# 08-DIPSwitches_I2C.net
KiCad netlist of a schematic drawn in Altium Designer
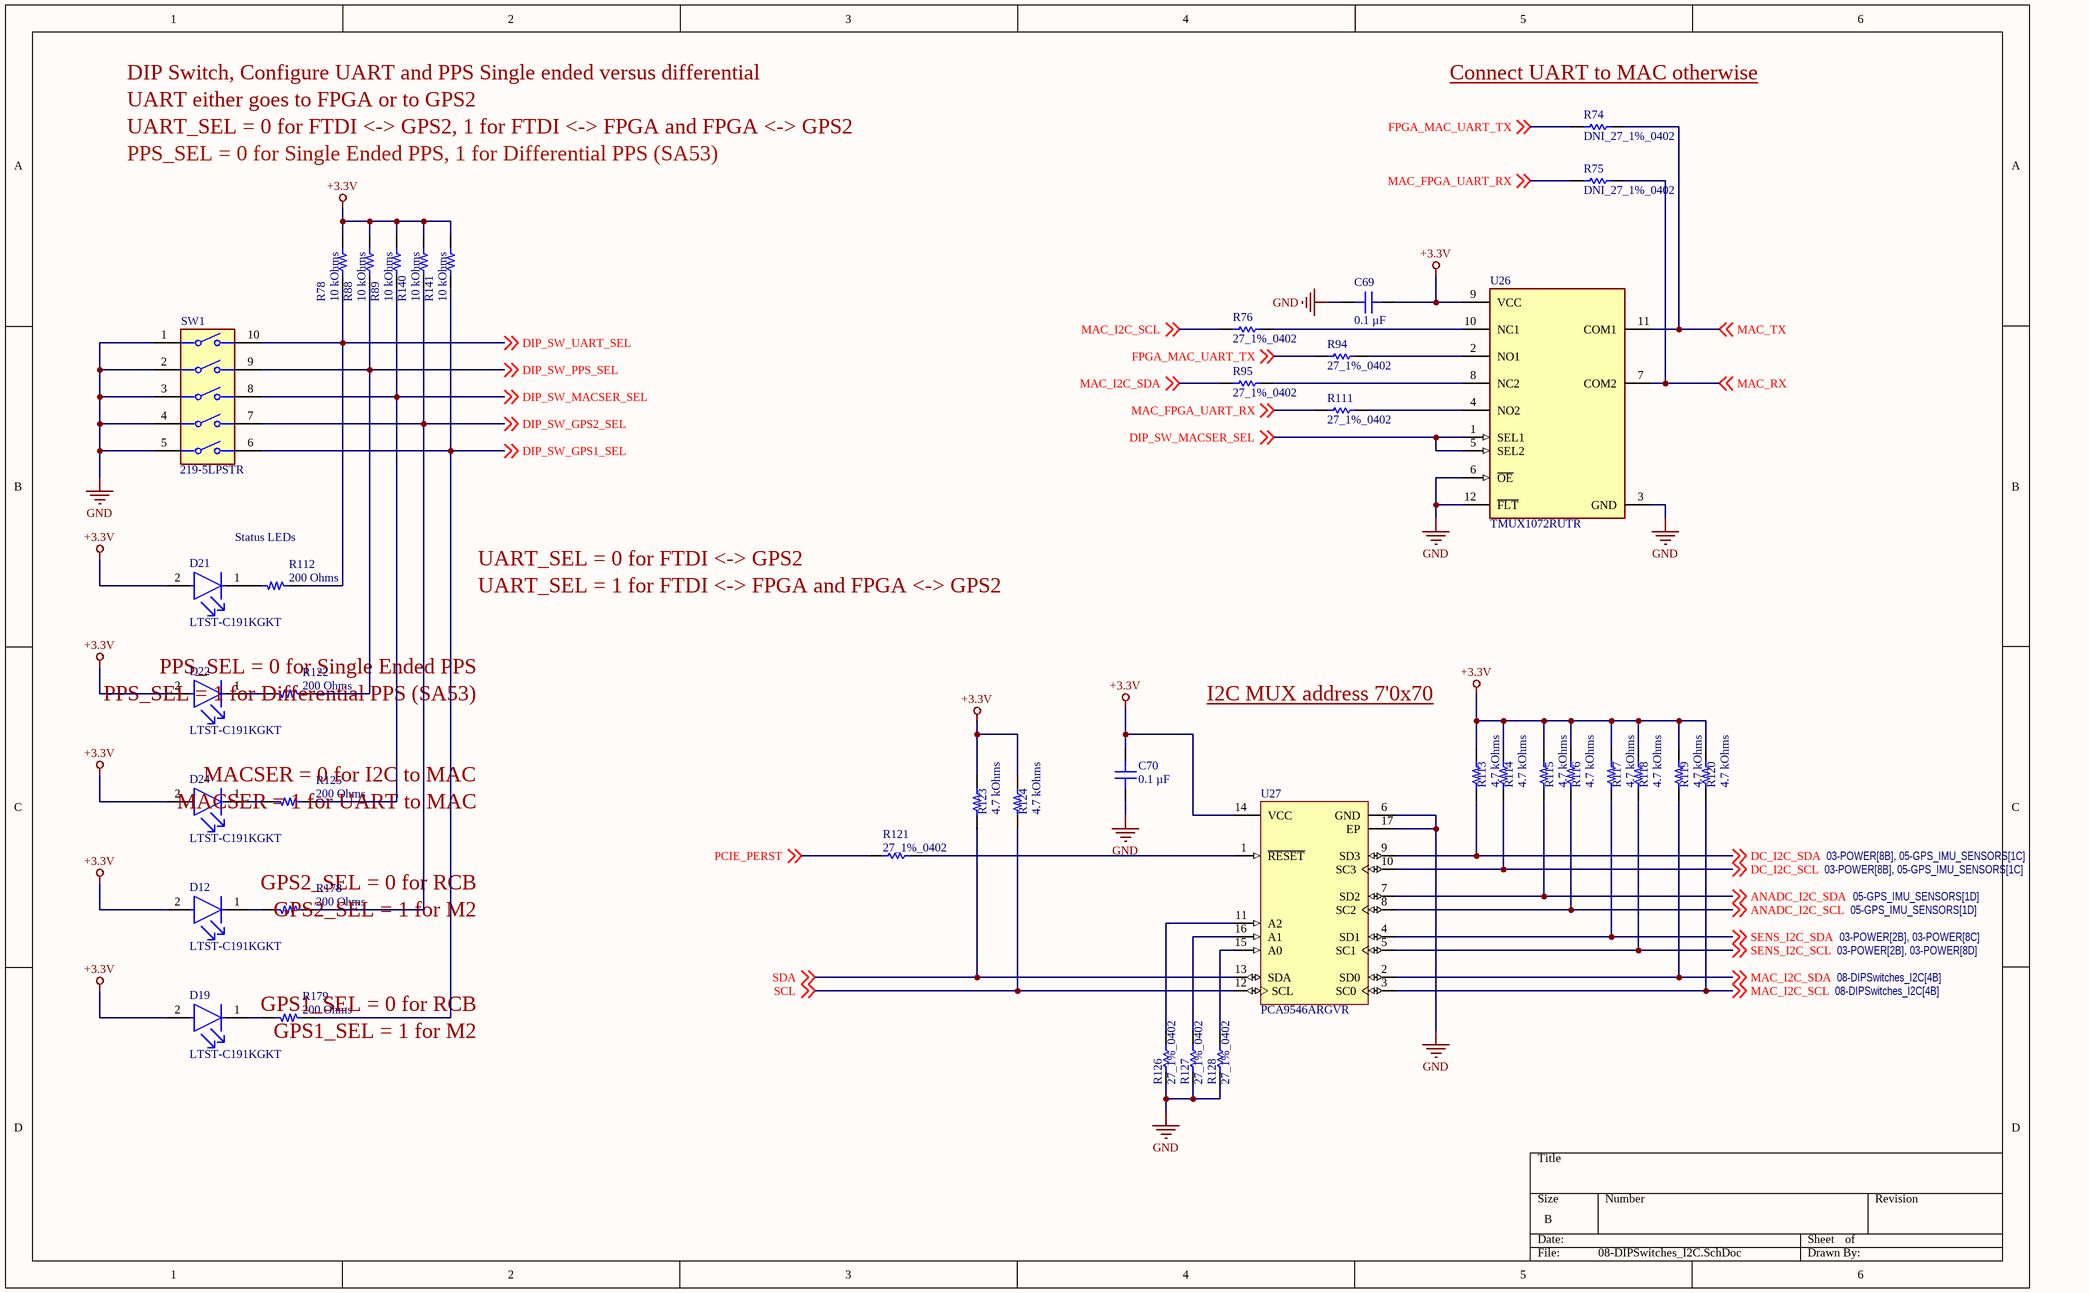
[diagram p0: 08-DIPSwitches_I2C.SchDoc]

(export (version "E")
  (design (tool "Eeschema 10.0.6"))
  (components
    (comp (ref "C69")
      (value "0.1 µF")
      (footprint "CAP 0402_1005")
      (description "CAP CER 0.1UF 50V X7R 0402")
      (fields (field (name "TOLERANCE") "±10%") (field (name "PART NUMBER") "CC0402KRX7R9BB104"))
      (libsource (lib "Celestial Altium Library - altium_library") (part "Capacitor"))
    )
    (comp (ref "C70")
      (value "0.1 µF")
      (footprint "CAP 0402_1005")
      (description "CAP CER 0.1UF 50V X7R 0402")
      (fields (field (name "TOLERANCE") "±10%") (field (name "PART NUMBER") "CC0402KRX7R9BB104"))
      (libsource (lib "Celestial Altium Library - altium_library") (part "Capacitor"))
    )
    (comp (ref "D12")
      (value "LTST-C191KGKT")
      (footprint "FP-LTST-C191KGKT-MFG")
      (description "LED GREEN CLEAR SMD")
      (libsource (lib "Altium Content Vault") (part "8706943c75ba83719d021d2fdc84c58"))
    )
    (comp (ref "D19")
      (value "LTST-C191KGKT")
      (footprint "FP-LTST-C191KGKT-MFG")
      (description "LED GREEN CLEAR SMD")
      (libsource (lib "Altium Content Vault") (part "8706943c75ba83719d021d2fdc84c58"))
    )
    (comp (ref "D21")
      (value "LTST-C191KGKT")
      (footprint "FP-LTST-C191KGKT-MFG")
      (description "LED GREEN CLEAR SMD")
      (libsource (lib "Altium Content Vault") (part "8706943c75ba83719d021d2fdc84c58"))
    )
    (comp (ref "D22")
      (value "LTST-C191KGKT")
      (footprint "FP-LTST-C191KGKT-MFG")
      (description "LED GREEN CLEAR SMD")
      (libsource (lib "Altium Content Vault") (part "8706943c75ba83719d021d2fdc84c58"))
    )
    (comp (ref "D24")
      (value "LTST-C191KGKT")
      (footprint "FP-LTST-C191KGKT-MFG")
      (description "LED GREEN CLEAR SMD")
      (libsource (lib "Altium Content Vault") (part "8706943c75ba83719d021d2fdc84c58"))
    )
    (comp (ref "R74")
      (value "DNI_27_1%_0402")
      (footprint "RESC1005X40X25NL05T05")
      (fields (field (name "PART NUMBER") "CRCW040227R0FKED") (field (name "MANUFACTURER") "Vishay Dale"))
      (libsource (lib "Altium Content Vault") (part "RES"))
    )
    (comp (ref "R75")
      (value "DNI_27_1%_0402")
      (footprint "RESC1005X40X25NL05T05")
      (fields (field (name "PART NUMBER") "CRCW040227R0FKED") (field (name "MANUFACTURER") "Vishay Dale"))
      (libsource (lib "Altium Content Vault") (part "RES"))
    )
    (comp (ref "R76")
      (value "27_1%_0402")
      (footprint "RESC1005X40X25NL05T05")
      (fields (field (name "PART NUMBER") "CRCW040227R0FKED") (field (name "MANUFACTURER") "Vishay Dale"))
      (libsource (lib "Altium Content Vault") (part "RES"))
    )
    (comp (ref "R78")
      (value "10 kOhms")
      (footprint "YAGEO RES 0402_1005")
      (description "RES 10K OHM 1% 1/16W 0402")
      (fields (field (name "PART NUMBER") "RC0402FR-0710KL") (field (name "MANUFACTURER") "Yageo"))
      (libsource (lib "Celestial Altium Library - altium_library") (part "Resistor"))
    )
    (comp (ref "R88")
      (value "10 kOhms")
      (footprint "YAGEO RES 0402_1005")
      (description "RES 10K OHM 1% 1/16W 0402")
      (fields (field (name "PART NUMBER") "RC0402FR-0710KL") (field (name "MANUFACTURER") "Yageo"))
      (libsource (lib "Celestial Altium Library - altium_library") (part "Resistor"))
    )
    (comp (ref "R89")
      (value "10 kOhms")
      (footprint "YAGEO RES 0402_1005")
      (description "RES 10K OHM 1% 1/16W 0402")
      (fields (field (name "PART NUMBER") "RC0402FR-0710KL") (field (name "MANUFACTURER") "Yageo"))
      (libsource (lib "Celestial Altium Library - altium_library") (part "Resistor"))
    )
    (comp (ref "R94")
      (value "27_1%_0402")
      (footprint "RESC1005X40X25NL05T05")
      (fields (field (name "PART NUMBER") "CRCW040227R0FKED") (field (name "MANUFACTURER") "Vishay Dale"))
      (libsource (lib "Altium Content Vault") (part "RES"))
    )
    (comp (ref "R95")
      (value "27_1%_0402")
      (footprint "RESC1005X40X25NL05T05")
      (fields (field (name "PART NUMBER") "CRCW040227R0FKED") (field (name "MANUFACTURER") "Vishay Dale"))
      (libsource (lib "Altium Content Vault") (part "RES"))
    )
    (comp (ref "R111")
      (value "27_1%_0402")
      (footprint "RESC1005X40X25NL05T05")
      (fields (field (name "PART NUMBER") "CRCW040227R0FKED") (field (name "MANUFACTURER") "Vishay Dale"))
      (libsource (lib "Altium Content Vault") (part "RES"))
    )
    (comp (ref "R112")
      (value "200 Ohms")
      (footprint "YAGEO RES 0402_1005")
      (description "RES 200 OHM 1% 1/16W 0402")
      (fields (field (name "MANUFACTURER") "Yageo") (field (name "PART NUMBER") "RC0402FR-07200RL"))
      (libsource (lib "Celestial Altium Library - altium_library") (part "Resistor"))
    )
    (comp (ref "R113")
      (value "4.7 kOhms")
      (footprint "YAGEO RES 0402_1005")
      (description "RES 4.7K OHM 1% 1/16W 0402")
      (fields (field (name "MANUFACTURER") "Yageo") (field (name "PART NUMBER") "RC0402FR-074K7L"))
      (libsource (lib "Celestial Altium Library - altium_library") (part "Resistor"))
    )
    (comp (ref "R114")
      (value "4.7 kOhms")
      (footprint "YAGEO RES 0402_1005")
      (description "RES 4.7K OHM 1% 1/16W 0402")
      (fields (field (name "MANUFACTURER") "Yageo") (field (name "PART NUMBER") "RC0402FR-074K7L"))
      (libsource (lib "Celestial Altium Library - altium_library") (part "Resistor"))
    )
    (comp (ref "R115")
      (value "4.7 kOhms")
      (footprint "YAGEO RES 0402_1005")
      (description "RES 4.7K OHM 1% 1/16W 0402")
      (fields (field (name "MANUFACTURER") "Yageo") (field (name "PART NUMBER") "RC0402FR-074K7L"))
      (libsource (lib "Celestial Altium Library - altium_library") (part "Resistor"))
    )
    (comp (ref "R116")
      (value "4.7 kOhms")
      (footprint "YAGEO RES 0402_1005")
      (description "RES 4.7K OHM 1% 1/16W 0402")
      (fields (field (name "MANUFACTURER") "Yageo") (field (name "PART NUMBER") "RC0402FR-074K7L"))
      (libsource (lib "Celestial Altium Library - altium_library") (part "Resistor"))
    )
    (comp (ref "R117")
      (value "4.7 kOhms")
      (footprint "YAGEO RES 0402_1005")
      (description "RES 4.7K OHM 1% 1/16W 0402")
      (fields (field (name "MANUFACTURER") "Yageo") (field (name "PART NUMBER") "RC0402FR-074K7L"))
      (libsource (lib "Celestial Altium Library - altium_library") (part "Resistor"))
    )
    (comp (ref "R118")
      (value "4.7 kOhms")
      (footprint "YAGEO RES 0402_1005")
      (description "RES 4.7K OHM 1% 1/16W 0402")
      (fields (field (name "MANUFACTURER") "Yageo") (field (name "PART NUMBER") "RC0402FR-074K7L"))
      (libsource (lib "Celestial Altium Library - altium_library") (part "Resistor"))
    )
    (comp (ref "R119")
      (value "4.7 kOhms")
      (footprint "YAGEO RES 0402_1005")
      (description "RES 4.7K OHM 1% 1/16W 0402")
      (fields (field (name "MANUFACTURER") "Yageo") (field (name "PART NUMBER") "RC0402FR-074K7L"))
      (libsource (lib "Celestial Altium Library - altium_library") (part "Resistor"))
    )
    (comp (ref "R120")
      (value "4.7 kOhms")
      (footprint "YAGEO RES 0402_1005")
      (description "RES 4.7K OHM 1% 1/16W 0402")
      (fields (field (name "MANUFACTURER") "Yageo") (field (name "PART NUMBER") "RC0402FR-074K7L"))
      (libsource (lib "Celestial Altium Library - altium_library") (part "Resistor"))
    )
    (comp (ref "R121")
      (value "27_1%_0402")
      (footprint "RESC1005X40X25NL05T05")
      (fields (field (name "PART NUMBER") "CRCW040227R0FKED") (field (name "MANUFACTURER") "Vishay Dale"))
      (libsource (lib "Altium Content Vault") (part "RES"))
    )
    (comp (ref "R122")
      (value "200 Ohms")
      (footprint "YAGEO RES 0402_1005")
      (description "RES 200 OHM 1% 1/16W 0402")
      (fields (field (name "MANUFACTURER") "Yageo") (field (name "PART NUMBER") "RC0402FR-07200RL"))
      (libsource (lib "Celestial Altium Library - altium_library") (part "Resistor"))
    )
    (comp (ref "R123")
      (value "4.7 kOhms")
      (footprint "YAGEO RES 0402_1005")
      (description "RES 4.7K OHM 1% 1/16W 0402")
      (fields (field (name "MANUFACTURER") "Yageo") (field (name "PART NUMBER") "RC0402FR-074K7L"))
      (libsource (lib "Celestial Altium Library - altium_library") (part "Resistor"))
    )
    (comp (ref "R124")
      (value "4.7 kOhms")
      (footprint "YAGEO RES 0402_1005")
      (description "RES 4.7K OHM 1% 1/16W 0402")
      (fields (field (name "MANUFACTURER") "Yageo") (field (name "PART NUMBER") "RC0402FR-074K7L"))
      (libsource (lib "Celestial Altium Library - altium_library") (part "Resistor"))
    )
    (comp (ref "R125")
      (value "200 Ohms")
      (footprint "YAGEO RES 0402_1005")
      (description "RES 200 OHM 1% 1/16W 0402")
      (fields (field (name "MANUFACTURER") "Yageo") (field (name "PART NUMBER") "RC0402FR-07200RL"))
      (libsource (lib "Celestial Altium Library - altium_library") (part "Resistor"))
    )
    (comp (ref "R126")
      (value "27_1%_0402")
      (footprint "RESC1005X40X25NL05T05")
      (fields (field (name "PART NUMBER") "CRCW040227R0FKED") (field (name "MANUFACTURER") "Vishay Dale"))
      (libsource (lib "Altium Content Vault") (part "RES"))
    )
    (comp (ref "R127")
      (value "27_1%_0402")
      (footprint "RESC1005X40X25NL05T05")
      (fields (field (name "PART NUMBER") "CRCW040227R0FKED") (field (name "MANUFACTURER") "Vishay Dale"))
      (libsource (lib "Altium Content Vault") (part "RES"))
    )
    (comp (ref "R128")
      (value "27_1%_0402")
      (footprint "RESC1005X40X25NL05T05")
      (fields (field (name "PART NUMBER") "CRCW040227R0FKED") (field (name "MANUFACTURER") "Vishay Dale"))
      (libsource (lib "Altium Content Vault") (part "RES"))
    )
    (comp (ref "R140")
      (value "10 kOhms")
      (footprint "YAGEO RES 0402_1005")
      (description "RES 10K OHM 1% 1/16W 0402")
      (fields (field (name "PART NUMBER") "RC0402FR-0710KL") (field (name "MANUFACTURER") "Yageo"))
      (libsource (lib "Celestial Altium Library - altium_library") (part "Resistor"))
    )
    (comp (ref "R141")
      (value "10 kOhms")
      (footprint "YAGEO RES 0402_1005")
      (description "RES 10K OHM 1% 1/16W 0402")
      (fields (field (name "PART NUMBER") "RC0402FR-0710KL") (field (name "MANUFACTURER") "Yageo"))
      (libsource (lib "Celestial Altium Library - altium_library") (part "Resistor"))
    )
    (comp (ref "R178")
      (value "200 Ohms")
      (footprint "YAGEO RES 0402_1005")
      (description "RES 200 OHM 1% 1/16W 0402")
      (fields (field (name "MANUFACTURER") "Yageo") (field (name "PART NUMBER") "RC0402FR-07200RL"))
      (libsource (lib "Celestial Altium Library - altium_library") (part "Resistor"))
    )
    (comp (ref "R179")
      (value "200 Ohms")
      (footprint "YAGEO RES 0402_1005")
      (description "RES 200 OHM 1% 1/16W 0402")
      (fields (field (name "MANUFACTURER") "Yageo") (field (name "PART NUMBER") "RC0402FR-07200RL"))
      (libsource (lib "Celestial Altium Library - altium_library") (part "Resistor"))
    )
    (comp (ref "SW1")
      (value "219-5LPSTR")
      (footprint "FP-219-5LPSTR-MFG")
      (description "SWITCH SLIDE DIP SPST 100MA 20V")
      (libsource (lib "Altium Content Vault") (part "5dac19a08bf10035f124d79214233cd"))
    )
    (comp (ref "U26")
      (value "TMUX1072RUTR")
      (footprint "FP-RUT0012A-MFG")
      (description "IC SWITCH SPDT DUAL 12UQFN")
      (libsource (lib "Altium Content Vault") (part "12a319ab100cd6cfe745e35972674f5"))
    )
    (comp (ref "U27")
      (value "PCA9546ARGVR")
      (footprint "RGV0016A_V")
      (fields (field (name "MANUFACTURER") "Texas Instruments"))
      (libsource (lib "Altium Content Vault") (part "TI-PCA9546A-VQFN_RGV-16"))
    )
  )
  (nets
    (net (code "1") (name "+3.3V") (class "Default")
      (node (ref "C69") (pin "2") (pinfunction "2_2") (pintype "passive"))
      (node (ref "C70") (pin "2") (pinfunction "2_2") (pintype "passive"))
      (node (ref "D12") (pin "2") (pinfunction "A_2") (pintype "passive"))
      (node (ref "D19") (pin "2") (pinfunction "A_2") (pintype "passive"))
      (node (ref "D21") (pin "2") (pinfunction "A_2") (pintype "passive"))
      (node (ref "D22") (pin "2") (pinfunction "A_2") (pintype "passive"))
      (node (ref "D24") (pin "2") (pinfunction "A_2") (pintype "passive"))
      (node (ref "R113") (pin "2") (pinfunction "2_2") (pintype "passive"))
      (node (ref "R114") (pin "2") (pinfunction "2_2") (pintype "passive"))
      (node (ref "R115") (pin "2") (pinfunction "2_2") (pintype "passive"))
      (node (ref "R116") (pin "2") (pinfunction "2_2") (pintype "passive"))
      (node (ref "R117") (pin "2") (pinfunction "2_2") (pintype "passive"))
      (node (ref "R118") (pin "2") (pinfunction "2_2") (pintype "passive"))
      (node (ref "R119") (pin "2") (pinfunction "2_2") (pintype "passive"))
      (node (ref "R120") (pin "2") (pinfunction "2_2") (pintype "passive"))
      (node (ref "R123") (pin "2") (pinfunction "2_2") (pintype "passive"))
      (node (ref "R124") (pin "2") (pinfunction "2_2") (pintype "passive"))
      (node (ref "R140") (pin "1") (pinfunction "1_1") (pintype "passive"))
      (node (ref "R141") (pin "1") (pinfunction "1_1") (pintype "passive"))
      (node (ref "R78") (pin "1") (pinfunction "1_1") (pintype "passive"))
      (node (ref "R88") (pin "1") (pinfunction "1_1") (pintype "passive"))
      (node (ref "R89") (pin "1") (pinfunction "1_1") (pintype "passive"))
      (node (ref "U26") (pin "9") (pinfunction "VCC_9") (pintype "power_in"))
      (node (ref "U27") (pin "14") (pinfunction "VCC_14") (pintype "power_in"))
    )
    (net (code "2") (name "ANADC_I2C_SCL") (class "Default")
      (node (ref "R116") (pin "1") (pinfunction "1_1") (pintype "passive"))
      (node (ref "U27") (pin "8") (pinfunction "SC2_8") (pintype "bidirectional"))
    )
    (net (code "3") (name "ANADC_I2C_SDA") (class "Default")
      (node (ref "R115") (pin "1") (pinfunction "1_1") (pintype "passive"))
      (node (ref "U27") (pin "7") (pinfunction "SD2_7") (pintype "bidirectional"))
    )
    (net (code "4") (name "DC_I2C_SCL") (class "Default")
      (node (ref "R114") (pin "1") (pinfunction "1_1") (pintype "passive"))
      (node (ref "U27") (pin "10") (pinfunction "SC3_10") (pintype "bidirectional"))
    )
    (net (code "5") (name "DC_I2C_SDA") (class "Default")
      (node (ref "R113") (pin "1") (pinfunction "1_1") (pintype "passive"))
      (node (ref "U27") (pin "9") (pinfunction "SD3_9") (pintype "bidirectional"))
    )
    (net (code "6") (name "DIP_SW_GPS1_SEL") (class "Default")
      (node (ref "R141") (pin "2") (pinfunction "2_2") (pintype "passive"))
      (node (ref "R179") (pin "2") (pinfunction "2_2") (pintype "passive"))
      (node (ref "SW1") (pin "6") (pinfunction "6_6") (pintype "passive"))
    )
    (net (code "7") (name "DIP_SW_GPS2_SEL") (class "Default")
      (node (ref "R140") (pin "2") (pinfunction "2_2") (pintype "passive"))
      (node (ref "R178") (pin "2") (pinfunction "2_2") (pintype "passive"))
      (node (ref "SW1") (pin "7") (pinfunction "7_7") (pintype "passive"))
    )
    (net (code "8") (name "DIP_SW_MACSER_SEL") (class "Default")
      (node (ref "R125") (pin "2") (pinfunction "2_2") (pintype "passive"))
      (node (ref "R89") (pin "2") (pinfunction "2_2") (pintype "passive"))
      (node (ref "SW1") (pin "8") (pinfunction "8_8") (pintype "passive"))
      (node (ref "U26") (pin "1") (pinfunction "SEL1_1") (pintype "input"))
      (node (ref "U26") (pin "5") (pinfunction "SEL2_5") (pintype "input"))
    )
    (net (code "9") (name "DIP_SW_PPS_SEL") (class "Default")
      (node (ref "R122") (pin "2") (pinfunction "2_2") (pintype "passive"))
      (node (ref "R88") (pin "2") (pinfunction "2_2") (pintype "passive"))
      (node (ref "SW1") (pin "9") (pinfunction "9_9") (pintype "passive"))
    )
    (net (code "10") (name "DIP_SW_UART_SEL") (class "Default")
      (node (ref "R112") (pin "2") (pinfunction "2_2") (pintype "passive"))
      (node (ref "R78") (pin "2") (pinfunction "2_2") (pintype "passive"))
      (node (ref "SW1") (pin "10") (pinfunction "10_10") (pintype "passive"))
    )
    (net (code "11") (name "FPGA_MAC_UART_TX") (class "Default")
      (node (ref "R74") (pin "1") (pinfunction "1_1") (pintype "passive"))
      (node (ref "R94") (pin "1") (pinfunction "1_1") (pintype "passive"))
    )
    (net (code "12") (name "GND") (class "Default")
      (node (ref "C69") (pin "1") (pinfunction "1_1") (pintype "passive"))
      (node (ref "C70") (pin "1") (pinfunction "1_1") (pintype "passive"))
      (node (ref "R126") (pin "1") (pinfunction "1_1") (pintype "passive"))
      (node (ref "R127") (pin "1") (pinfunction "1_1") (pintype "passive"))
      (node (ref "R128") (pin "1") (pinfunction "1_1") (pintype "passive"))
      (node (ref "SW1") (pin "1") (pinfunction "1_1") (pintype "passive"))
      (node (ref "SW1") (pin "2") (pinfunction "2_2") (pintype "passive"))
      (node (ref "SW1") (pin "3") (pinfunction "3_3") (pintype "passive"))
      (node (ref "SW1") (pin "4") (pinfunction "4_4") (pintype "passive"))
      (node (ref "SW1") (pin "5") (pinfunction "5_5") (pintype "passive"))
      (node (ref "U26") (pin "12") (pinfunction "~{FLT}_12") (pintype "open_collector"))
      (node (ref "U26") (pin "3") (pinfunction "GND_3") (pintype "power_in"))
      (node (ref "U26") (pin "6") (pinfunction "~{OE}_6") (pintype "input"))
      (node (ref "U27") (pin "17") (pinfunction "EP_17") (pintype "passive"))
      (node (ref "U27") (pin "6") (pinfunction "GND_6") (pintype "power_in"))
    )
    (net (code "13") (name "MAC_FPGA_UART_RX") (class "Default")
      (node (ref "R111") (pin "1") (pinfunction "1_1") (pintype "passive"))
      (node (ref "R75") (pin "1") (pinfunction "1_1") (pintype "passive"))
    )
    (net (code "14") (name "MAC_I2C_SCL") (class "Default")
      (node (ref "R120") (pin "1") (pinfunction "1_1") (pintype "passive"))
      (node (ref "R76") (pin "1") (pinfunction "1_1") (pintype "passive"))
      (node (ref "U27") (pin "3") (pinfunction "SC0_3") (pintype "bidirectional"))
    )
    (net (code "15") (name "MAC_I2C_SDA") (class "Default")
      (node (ref "R119") (pin "1") (pinfunction "1_1") (pintype "passive"))
      (node (ref "R95") (pin "1") (pinfunction "1_1") (pintype "passive"))
      (node (ref "U27") (pin "2") (pinfunction "SD0_2") (pintype "bidirectional"))
    )
    (net (code "16") (name "MAC_RX") (class "Default")
      (node (ref "R75") (pin "2") (pinfunction "2_2") (pintype "passive"))
      (node (ref "U26") (pin "7") (pinfunction "COM2_7") (pintype "passive"))
    )
    (net (code "17") (name "MAC_TX") (class "Default")
      (node (ref "R74") (pin "2") (pinfunction "2_2") (pintype "passive"))
      (node (ref "U26") (pin "11") (pinfunction "COM1_11") (pintype "passive"))
    )
    (net (code "18") (name "Net-(D12-C)") (class "Default")
      (node (ref "D12") (pin "1") (pinfunction "C_1") (pintype "passive"))
      (node (ref "R178") (pin "1") (pinfunction "1_1") (pintype "passive"))
    )
    (net (code "19") (name "Net-(D19-C)") (class "Default")
      (node (ref "D19") (pin "1") (pinfunction "C_1") (pintype "passive"))
      (node (ref "R179") (pin "1") (pinfunction "1_1") (pintype "passive"))
    )
    (net (code "20") (name "Net-(D21-C)") (class "Default")
      (node (ref "D21") (pin "1") (pinfunction "C_1") (pintype "passive"))
      (node (ref "R112") (pin "1") (pinfunction "1_1") (pintype "passive"))
    )
    (net (code "21") (name "Net-(D22-C)") (class "Default")
      (node (ref "D22") (pin "1") (pinfunction "C_1") (pintype "passive"))
      (node (ref "R122") (pin "1") (pinfunction "1_1") (pintype "passive"))
    )
    (net (code "22") (name "Net-(D24-C)") (class "Default")
      (node (ref "D24") (pin "1") (pinfunction "C_1") (pintype "passive"))
      (node (ref "R125") (pin "1") (pinfunction "1_1") (pintype "passive"))
    )
    (net (code "23") (name "Net-(U26-NC1)") (class "Default")
      (node (ref "R76") (pin "2") (pinfunction "2_2") (pintype "passive"))
      (node (ref "U26") (pin "10") (pinfunction "NC1_10") (pintype "passive"))
    )
    (net (code "24") (name "Net-(U26-NC2)") (class "Default")
      (node (ref "R95") (pin "2") (pinfunction "2_2") (pintype "passive"))
      (node (ref "U26") (pin "8") (pinfunction "NC2_8") (pintype "passive"))
    )
    (net (code "25") (name "Net-(U26-NO1)") (class "Default")
      (node (ref "R94") (pin "2") (pinfunction "2_2") (pintype "passive"))
      (node (ref "U26") (pin "2") (pinfunction "NO1_2") (pintype "passive"))
    )
    (net (code "26") (name "Net-(U26-NO2)") (class "Default")
      (node (ref "R111") (pin "2") (pinfunction "2_2") (pintype "passive"))
      (node (ref "U26") (pin "4") (pinfunction "NO2_4") (pintype "passive"))
    )
    (net (code "27") (name "Net-(U27-A0)") (class "Default")
      (node (ref "R128") (pin "2") (pinfunction "2_2") (pintype "passive"))
      (node (ref "U27") (pin "15") (pinfunction "A0_15") (pintype "input"))
    )
    (net (code "28") (name "Net-(U27-A1)") (class "Default")
      (node (ref "R127") (pin "2") (pinfunction "2_2") (pintype "passive"))
      (node (ref "U27") (pin "16") (pinfunction "A1_16") (pintype "input"))
    )
    (net (code "29") (name "Net-(U27-A2)") (class "Default")
      (node (ref "R126") (pin "2") (pinfunction "2_2") (pintype "passive"))
      (node (ref "U27") (pin "11") (pinfunction "A2_11") (pintype "input"))
    )
    (net (code "30") (name "Net-(U27-~{RESET})") (class "Default")
      (node (ref "R121") (pin "2") (pinfunction "2_2") (pintype "passive"))
      (node (ref "U27") (pin "1") (pinfunction "~{RESET}_1") (pintype "input"))
    )
    (net (code "31") (name "PCIE_PERST") (class "Default")
      (node (ref "R121") (pin "1") (pinfunction "1_1") (pintype "passive"))
    )
    (net (code "32") (name "SCL") (class "Default")
      (node (ref "R124") (pin "1") (pinfunction "1_1") (pintype "passive"))
      (node (ref "U27") (pin "12") (pinfunction "SCL_12") (pintype "bidirectional"))
    )
    (net (code "33") (name "SDA") (class "Default")
      (node (ref "R123") (pin "1") (pinfunction "1_1") (pintype "passive"))
      (node (ref "U27") (pin "13") (pinfunction "SDA_13") (pintype "bidirectional"))
    )
    (net (code "34") (name "SENS_I2C_SCL") (class "Default")
      (node (ref "R118") (pin "1") (pinfunction "1_1") (pintype "passive"))
      (node (ref "U27") (pin "5") (pinfunction "SC1_5") (pintype "bidirectional"))
    )
    (net (code "35") (name "SENS_I2C_SDA") (class "Default")
      (node (ref "R117") (pin "1") (pinfunction "1_1") (pintype "passive"))
      (node (ref "U27") (pin "4") (pinfunction "SD1_4") (pintype "bidirectional"))
    )
  )
)
